# USB-C_Protection.net
KiCad netlist of a schematic drawn in Altium Designer
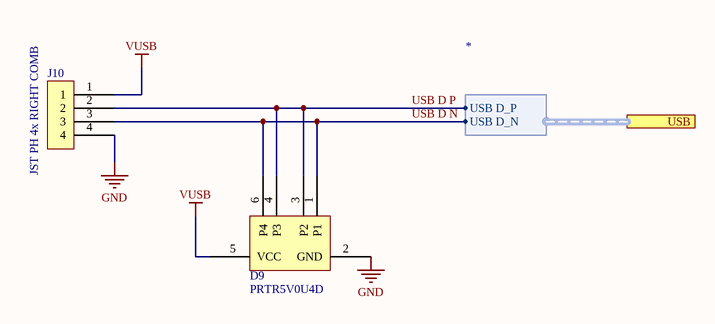
[diagram p0: USB-C Protection.SchDoc]

(export (version "E")
  (design (tool "Eeschema 10.0.6"))
  (components
    (comp (ref "D9")
      (value "PRTR5V0U4D")
      (footprint "SC-47")
      (description "Clamp Ipp Tvs Diode Surface Mount 6-TSOP")
      (libsource (lib "QUTMS-MCISOLibrary") (part "PRTR5V0U4D"))
    )
    (comp (ref "J10")
      (value "JST PH 4x RIGHT COMB")
      (footprint "JST PH 4x RIGHT COMB")
      (libsource (lib "QUTMS-MCISOLibrary") (part "JST PH 4x RIGHT COMB"))
    )
  )
  (nets
    (net (code "2") (name "/USB D N") (class "Default")
      (node (ref "D9") (pin "1") (pinfunction "P1_1") (pintype "passive"))
      (node (ref "D9") (pin "6") (pinfunction "P4_6") (pintype "passive"))
      (node (ref "J10") (pin "3") (pinfunction "3_3") (pintype "passive"))
    )
    (net (code "3") (name "/USB D P") (class "Default")
      (node (ref "D9") (pin "3") (pinfunction "P2_3") (pintype "passive"))
      (node (ref "D9") (pin "4") (pinfunction "P3_4") (pintype "passive"))
      (node (ref "J10") (pin "2") (pinfunction "2_2") (pintype "passive"))
    )
    (net (code "5") (name "GND") (class "Default")
      (node (ref "D9") (pin "2") (pinfunction "GND_2") (pintype "passive"))
      (node (ref "J10") (pin "4") (pinfunction "4_4") (pintype "passive"))
    )
    (net (code "6") (name "VUSB") (class "Default")
      (node (ref "D9") (pin "5") (pinfunction "VCC_5") (pintype "passive"))
      (node (ref "J10") (pin "1") (pinfunction "1_1") (pintype "passive"))
    )
  )
)
